# labwiz-module_servo_dual.net
KiCad netlist of a schematic drawn in EAGLE
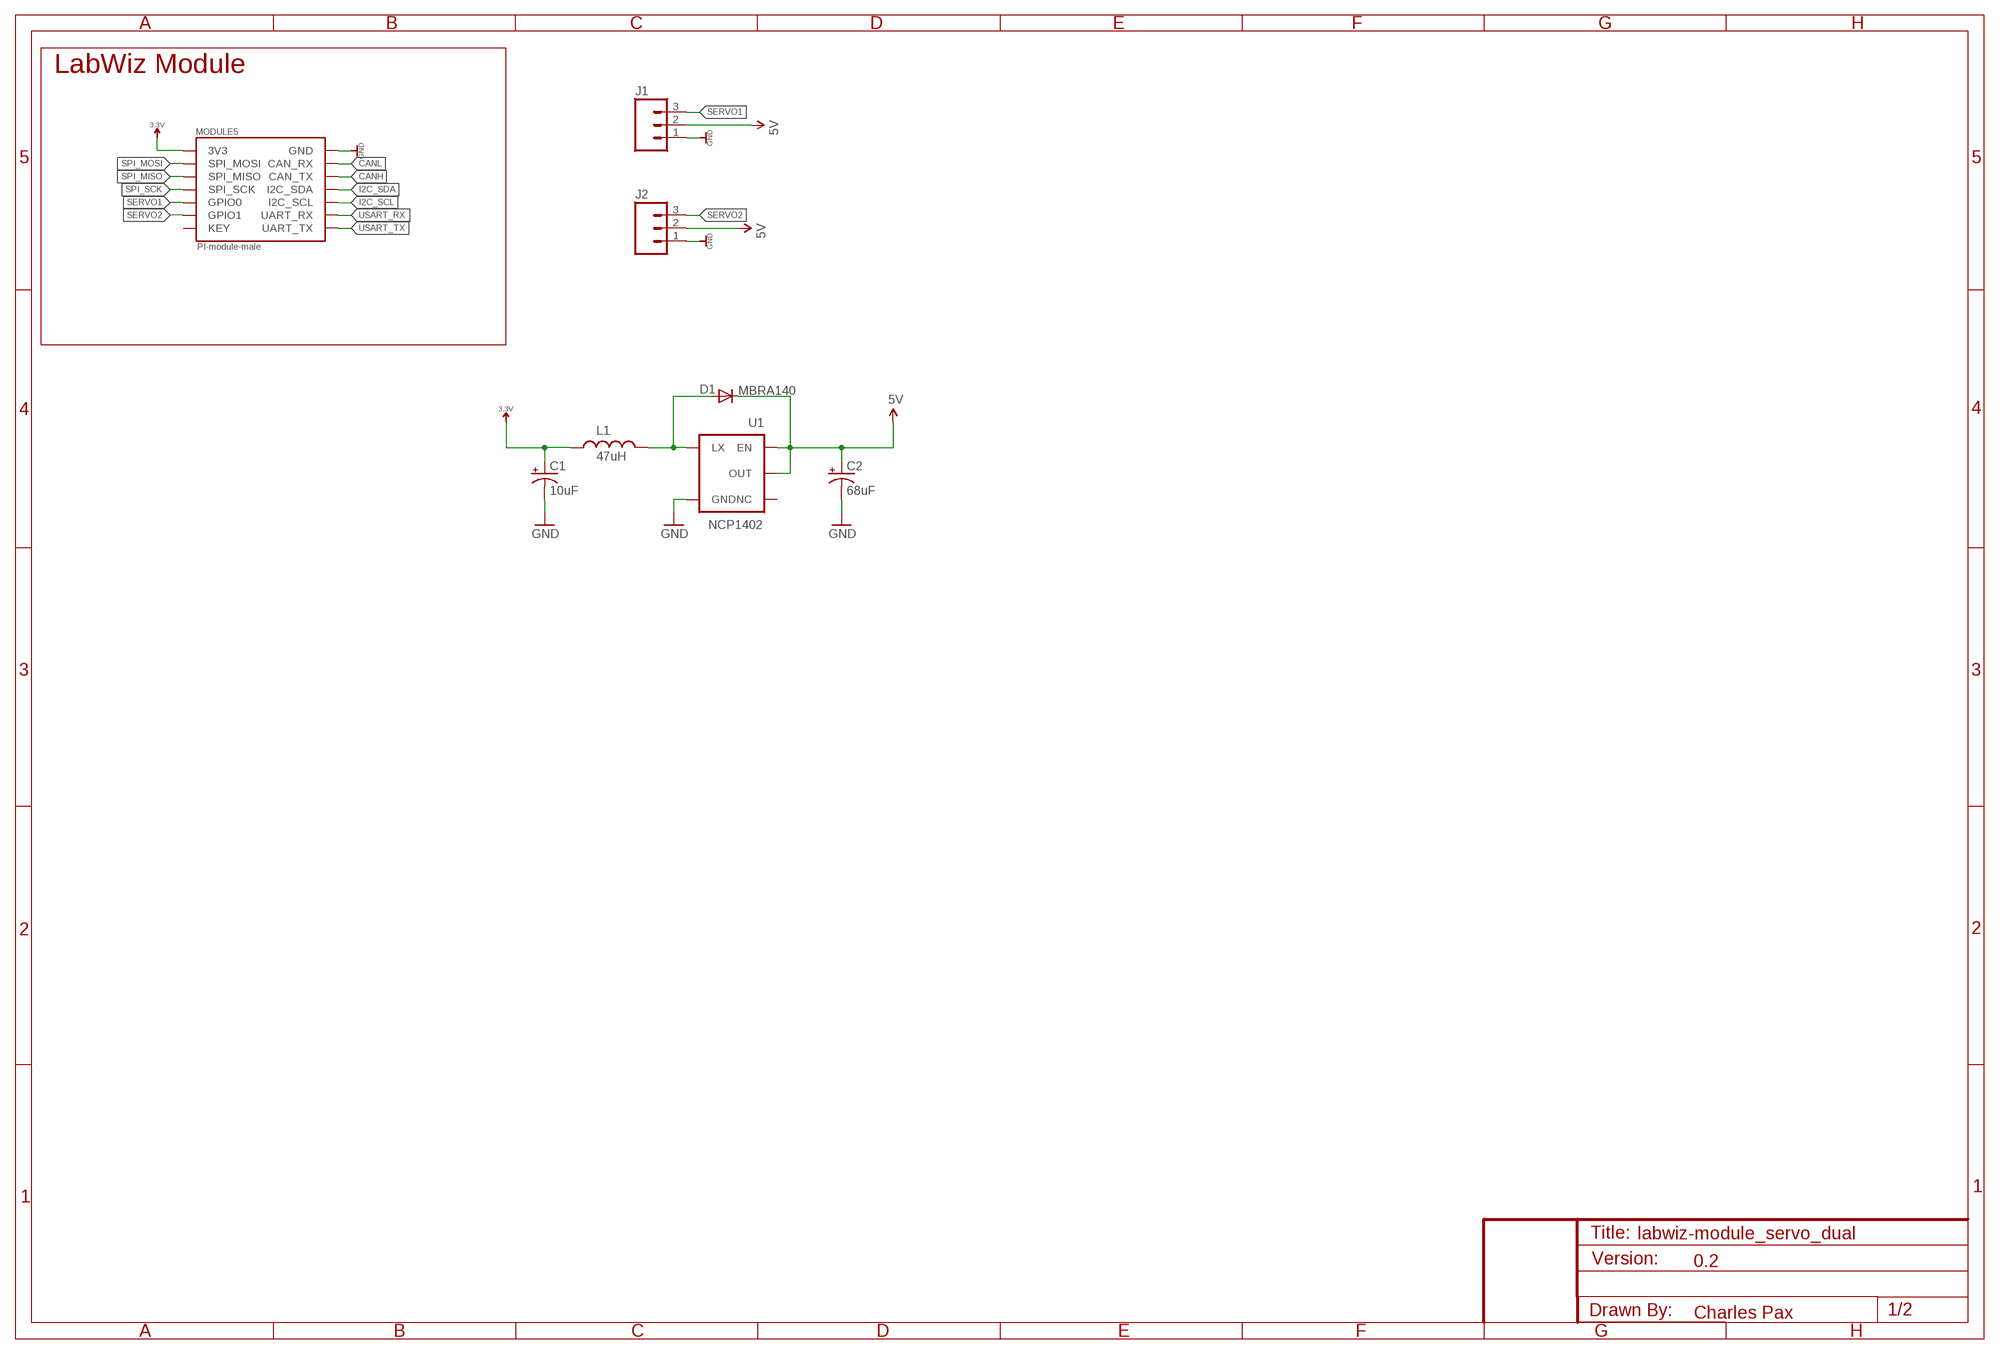
[diagram p0: schematic, sheet 1]

(export (version "E")
  (design (tool "Eeschema 10.0.6"))
  (components
    (comp (ref "C1")
      (value "10uF")
      (footprint "eagle-import:EIA3216")
      (libsource (lib "eagle-import") (part "CAP_POL1206"))
    )
    (comp (ref "C2")
      (value "68uF")
      (footprint "eagle-import:EIA3528")
      (libsource (lib "eagle-import") (part "CAP_POL3528"))
    )
    (comp (ref "D1")
      (value "MBRA140")
      (footprint "eagle-import:SMA-DIODE")
      (libsource (lib "eagle-import") (part "DIODESMA"))
    )
    (comp (ref "J1")
      (value "M031X03_SMD_RA_MALE_POST_SMALLEST")
      (footprint "eagle-import:1X03_SMD_RA_MALE_POST_SMALLEST")
      (libsource (lib "eagle-import") (part "M031X03_SMD_RA_MALE_POST_SMALLEST"))
    )
    (comp (ref "J2")
      (value "M031X03_SMD_RA_MALE_POST_SMALLEST")
      (footprint "eagle-import:1X03_SMD_RA_MALE_POST_SMALLEST")
      (libsource (lib "eagle-import") (part "M031X03_SMD_RA_MALE_POST_SMALLEST"))
    )
    (comp (ref "L1")
      (value "47uH")
      (footprint "eagle-import:CR54")
      (libsource (lib "eagle-import") (part "INDUCTORCR54"))
    )
    (comp (ref "MODULE5")
      (value "PI-module-male")
      (footprint "eagle-import:M07X2_2MM_EDGE")
      (fields (field (name "MF") "Pax Instruments") (field (name "MPN") "PIxxxx"))
      (libsource (lib "eagle-import") (part "PAX_MODULE_EDGE_MALE_MODULE"))
    )
    (comp (ref "U1")
      (value "NCP1402")
      (footprint "eagle-import:SOT23-5")
      (libsource (lib "eagle-import") (part "V_REG_NCP1400SOT23-5"))
    )
  )
  (nets
    (net (code "1") (name "3.3V") (class "Default")
      (node (ref "C1") (pin "A") (pinfunction "+_A") (pintype "passive"))
      (node (ref "L1") (pin "P$1") (pinfunction "1_P$1") (pintype "passive"))
      (node (ref "MODULE5") (pin "P$13") (pinfunction "3V3_P$13") (pintype "power_in"))
    )
    (net (code "2") (name "5V") (class "Default")
      (node (ref "C2") (pin "A") (pinfunction "+_A") (pintype "passive"))
      (node (ref "D1") (pin "C") (pinfunction "C_C") (pintype "passive"))
      (node (ref "J1") (pin "2") (pinfunction "2_2") (pintype "passive"))
      (node (ref "J2") (pin "2") (pinfunction "2_2") (pintype "passive"))
      (node (ref "U1") (pin "1") (pinfunction "EN_1") (pintype "input"))
      (node (ref "U1") (pin "2") (pinfunction "OUT_2") (pintype "passive"))
    )
    (net (code "3") (name "CANH") (class "Default")
      (node (ref "MODULE5") (pin "P$10") (pinfunction "CAN_TX_P$10") (pintype "bidirectional"))
    )
    (net (code "4") (name "CANL") (class "Default")
      (node (ref "MODULE5") (pin "P$12") (pinfunction "CAN_RX_P$12") (pintype "bidirectional"))
    )
    (net (code "5") (name "GND") (class "Default")
      (node (ref "C1") (pin "C") (pinfunction "-_C") (pintype "passive"))
      (node (ref "C2") (pin "C") (pinfunction "-_C") (pintype "passive"))
      (node (ref "J1") (pin "1") (pinfunction "1_1") (pintype "passive"))
      (node (ref "J2") (pin "1") (pinfunction "1_1") (pintype "passive"))
      (node (ref "MODULE5") (pin "P$14") (pinfunction "GND_P$14") (pintype "power_in"))
      (node (ref "U1") (pin "4") (pinfunction "GND_4") (pintype "input"))
    )
    (net (code "6") (name "I2C_SCL") (class "Default")
      (node (ref "MODULE5") (pin "P$6") (pinfunction "I2C_SCL_P$6") (pintype "bidirectional"))
    )
    (net (code "7") (name "I2C_SDA") (class "Default")
      (node (ref "MODULE5") (pin "P$8") (pinfunction "I2C_SDA_P$8") (pintype "bidirectional"))
    )
    (net (code "8") (name "Net-(L1-2)") (class "Default")
      (node (ref "D1") (pin "A") (pinfunction "A_A") (pintype "passive"))
      (node (ref "L1") (pin "P$2") (pinfunction "2_P$2") (pintype "passive"))
      (node (ref "U1") (pin "5") (pinfunction "LX_5") (pintype "input"))
    )
    (net (code "9") (name "SERVO1") (class "Default")
      (node (ref "J1") (pin "3") (pinfunction "3_3") (pintype "passive"))
      (node (ref "MODULE5") (pin "P$5") (pinfunction "GPIO0_P$5") (pintype "bidirectional"))
    )
    (net (code "10") (name "SERVO2") (class "Default")
      (node (ref "J2") (pin "3") (pinfunction "3_3") (pintype "passive"))
      (node (ref "MODULE5") (pin "P$3") (pinfunction "GPIO1_P$3") (pintype "bidirectional"))
    )
    (net (code "11") (name "SPI_MISO") (class "Default")
      (node (ref "MODULE5") (pin "P$9") (pinfunction "SPI_MISO_P$9") (pintype "bidirectional"))
    )
    (net (code "12") (name "SPI_MOSI") (class "Default")
      (node (ref "MODULE5") (pin "P$11") (pinfunction "SPI_MOSI_P$11") (pintype "bidirectional"))
    )
    (net (code "13") (name "SPI_SCK") (class "Default")
      (node (ref "MODULE5") (pin "P$7") (pinfunction "SPI_SCK_P$7") (pintype "bidirectional"))
    )
    (net (code "14") (name "USART_RX") (class "Default")
      (node (ref "MODULE5") (pin "P$4") (pinfunction "UART_RX_P$4") (pintype "bidirectional"))
    )
    (net (code "15") (name "USART_TX") (class "Default")
      (node (ref "MODULE5") (pin "P$2") (pinfunction "UART_TX_P$2") (pintype "bidirectional"))
    )
    (net (code "16") (name "unconnected-(MODULE5-KEY-PadP$1)") (class "Default")
      (node (ref "MODULE5") (pin "P$1") (pinfunction "KEY_P$1") (pintype "no_connect"))
    )
    (net (code "17") (name "unconnected-(U1-NC-Pad3)") (class "Default")
      (node (ref "U1") (pin "3") (pinfunction "NC_3") (pintype "input"))
    )
  )
)
